# PCB_BLU1.net
KiCad netlist of a schematic drawn in Altium Designer
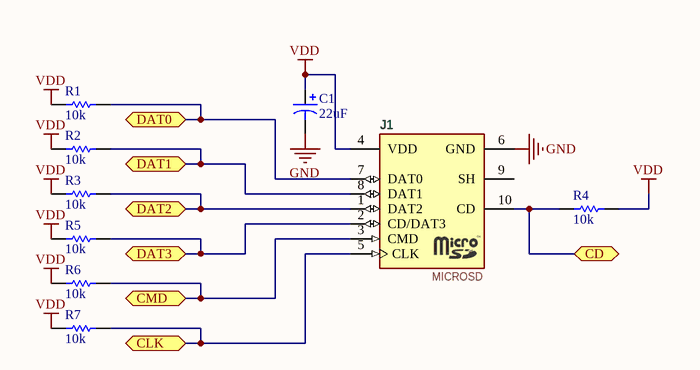
[diagram p0: PCB_BLU1.SchDoc]

(export (version "E")
  (design (tool "Eeschema 10.0.6"))
  (components
    (comp (ref "C1")
      (value "22uF")
      (footprint "6032")
      (fields (field (name "PUBLISHER") "Altium Limited"))
      (libsource (lib "Vishay Sprague Tantalum Chip Capacitor") (part "CWR11DH226M"))
    )
    (comp (ref "J1")
      (value "MICROSD")
      (footprint "MICROSD")
      (description "Memory Card Connectors Molex 504528-0892")
      (libsource (lib "MICROSD") (part "MICROSD"))
    )
    (comp (ref "R1")
      (value "10k")
      (footprint "RES0201R")
      (description "Resistor")
      (libsource (lib "PassiveSMT") (part "Resistor1"))
    )
    (comp (ref "R2")
      (value "10k")
      (footprint "RES0201R")
      (description "Resistor")
      (libsource (lib "PassiveSMT") (part "Resistor1"))
    )
    (comp (ref "R3")
      (value "10k")
      (footprint "RES0201R")
      (description "Resistor")
      (libsource (lib "PassiveSMT") (part "Resistor1"))
    )
    (comp (ref "R4")
      (value "10k")
      (footprint "RES0201R")
      (description "Resistor")
      (libsource (lib "PassiveSMT") (part "Resistor1"))
    )
    (comp (ref "R5")
      (value "10k")
      (footprint "RES0201R")
      (description "Resistor")
      (libsource (lib "PassiveSMT") (part "Resistor1"))
    )
    (comp (ref "R6")
      (value "10k")
      (footprint "RES0201R")
      (description "Resistor")
      (libsource (lib "PassiveSMT") (part "Resistor1"))
    )
    (comp (ref "R7")
      (value "10k")
      (footprint "RES0201R")
      (description "Resistor")
      (libsource (lib "PassiveSMT") (part "Resistor1"))
    )
  )
  (nets
    (net (code "1") (name "/CD") (class "Default")
      (node (ref "J1") (pin "10") (pinfunction "CD_10") (pintype "passive"))
      (node (ref "R4") (pin "2") (pinfunction "2_2") (pintype "passive"))
    )
    (net (code "2") (name "/CLK") (class "Default")
      (node (ref "J1") (pin "5") (pinfunction "CLK_5") (pintype "input"))
      (node (ref "R7") (pin "1") (pinfunction "1_1") (pintype "passive"))
    )
    (net (code "3") (name "/CMD") (class "Default")
      (node (ref "J1") (pin "3") (pinfunction "CMD_3") (pintype "input"))
      (node (ref "R6") (pin "1") (pinfunction "1_1") (pintype "passive"))
    )
    (net (code "4") (name "/DAT0") (class "Default")
      (node (ref "J1") (pin "7") (pinfunction "DAT0_7") (pintype "bidirectional"))
      (node (ref "R1") (pin "1") (pinfunction "1_1") (pintype "passive"))
    )
    (net (code "5") (name "/DAT1") (class "Default")
      (node (ref "J1") (pin "8") (pinfunction "DAT1_8") (pintype "bidirectional"))
      (node (ref "R2") (pin "1") (pinfunction "1_1") (pintype "passive"))
    )
    (net (code "6") (name "/DAT2") (class "Default")
      (node (ref "J1") (pin "1") (pinfunction "DAT2_1") (pintype "bidirectional"))
      (node (ref "R3") (pin "1") (pinfunction "1_1") (pintype "passive"))
    )
    (net (code "7") (name "/DAT3") (class "Default")
      (node (ref "J1") (pin "2") (pinfunction "CD/DAT3_2") (pintype "bidirectional"))
      (node (ref "R5") (pin "1") (pinfunction "1_1") (pintype "passive"))
    )
    (net (code "8") (name "GND") (class "Default")
      (node (ref "C1") (pin "2") (pinfunction "2_2") (pintype "passive"))
      (node (ref "J1") (pin "6") (pinfunction "GND_6") (pintype "power_in"))
    )
    (net (code "9") (name "VDD") (class "Default")
      (node (ref "C1") (pin "1") (pinfunction "1_1") (pintype "passive"))
      (node (ref "J1") (pin "4") (pinfunction "VDD_4") (pintype "power_in"))
      (node (ref "R1") (pin "2") (pinfunction "2_2") (pintype "passive"))
      (node (ref "R2") (pin "2") (pinfunction "2_2") (pintype "passive"))
      (node (ref "R3") (pin "2") (pinfunction "2_2") (pintype "passive"))
      (node (ref "R4") (pin "1") (pinfunction "1_1") (pintype "passive"))
      (node (ref "R5") (pin "2") (pinfunction "2_2") (pintype "passive"))
      (node (ref "R6") (pin "2") (pinfunction "2_2") (pintype "passive"))
      (node (ref "R7") (pin "2") (pinfunction "2_2") (pintype "passive"))
    )
    (net (code "10") (name "unconnected-(J1-SH-Pad9)") (class "Default")
      (node (ref "J1") (pin "9") (pinfunction "SH_9") (pintype "passive"))
    )
  )
)
